# MCU.net
KiCad netlist of a schematic drawn in Altium Designer
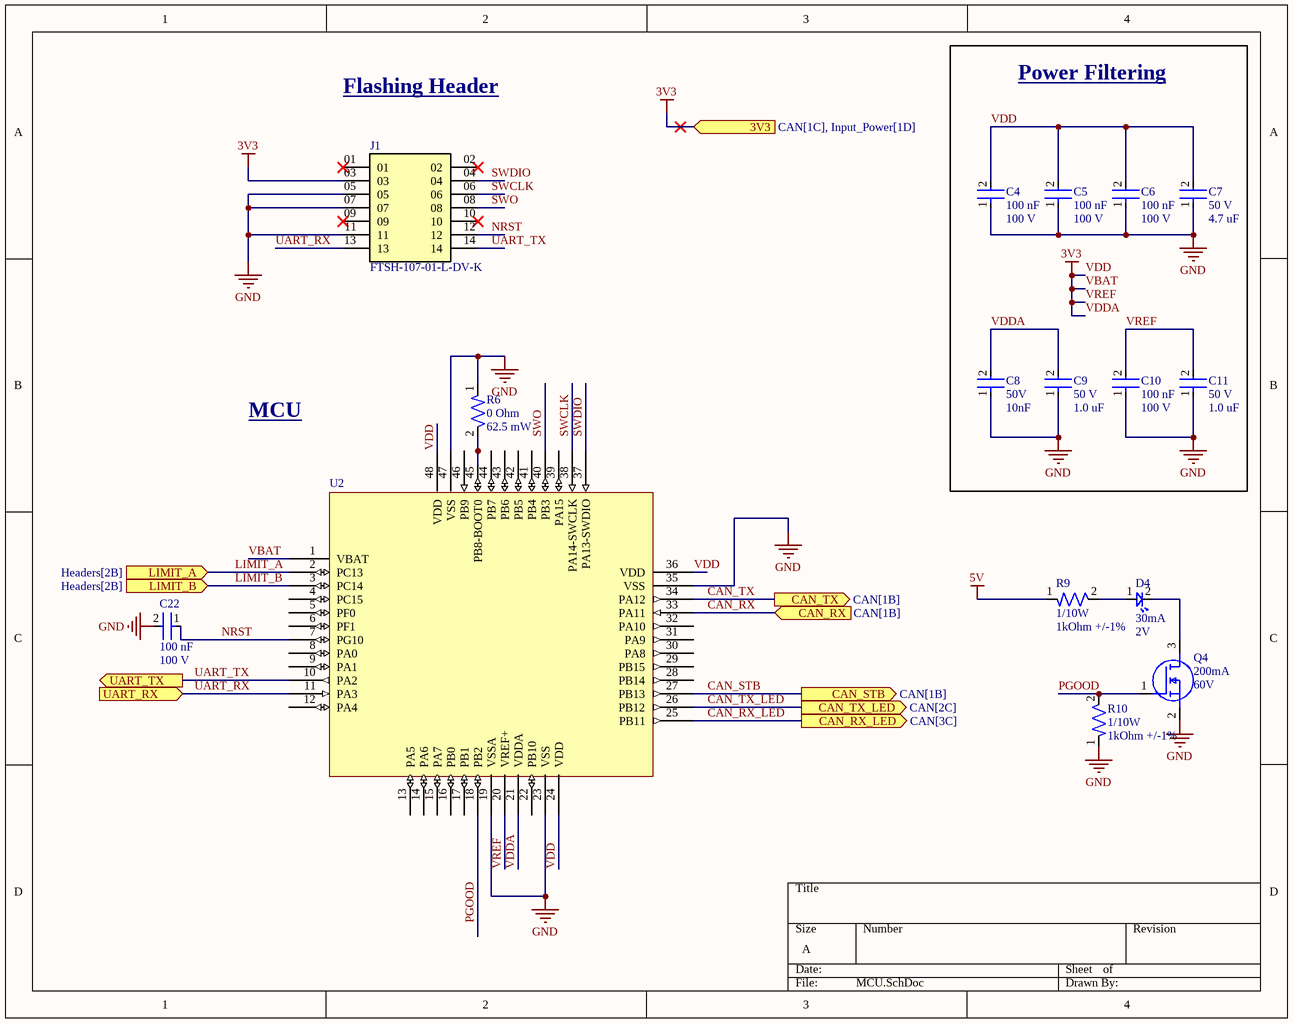
[diagram p0: MCU.SchDoc]

(export (version "E")
  (design (tool "Eeschema 10.0.6"))
  (components
    (comp (ref "C4")
      (value "CC0603KRX7R0BB104")
      (footprint "CAP-0603")
      (description "CAP CER 0.1UF 100V X7R 0603")
      (fields (field (name "CAPACITANCE") "100 nF") (field (name "VOLTAGE") "100 V"))
      (libsource (lib "JLC_25") (part "CAP-100N-0001"))
    )
    (comp (ref "C5")
      (value "CC0603KRX7R0BB104")
      (footprint "CAP-0603")
      (description "CAP CER 0.1UF 100V X7R 0603")
      (fields (field (name "CAPACITANCE") "100 nF") (field (name "VOLTAGE") "100 V"))
      (libsource (lib "JLC_25") (part "CAP-100N-0001"))
    )
    (comp (ref "C6")
      (value "CC0603KRX7R0BB104")
      (footprint "CAP-0603")
      (description "CAP CER 0.1UF 100V X7R 0603")
      (fields (field (name "CAPACITANCE") "100 nF") (field (name "VOLTAGE") "100 V"))
      (libsource (lib "JLC_25") (part "CAP-100N-0001"))
    )
    (comp (ref "C7")
      (value "CC0805KKX5R9BB475")
      (footprint "CAP-0805")
      (description "CAP CER 4.7UF 50V X5R 0805")
      (fields (field (name "VOLTAGE") "50 V") (field (name "CAPACITANCE") "4.7 uF"))
      (libsource (lib "JLC_25") (part "CAP-4.7U-0002"))
    )
    (comp (ref "C8")
      (value "GRM2195C1H103JA01D")
      (footprint "CAP-0805")
      (description "CAP CER 10000PF 50V C0G/NP0 0805")
      (fields (field (name "VOLTAGE") "50V") (field (name "CAPACITANCE") "10nF"))
      (libsource (lib "JLC_25") (part "CAP-10N-0001"))
    )
    (comp (ref "C9")
      (value "CC0805KKX7R9BB105")
      (footprint "CAP-0805")
      (description "CAP CER 1UF 50V X7R 0805")
      (fields (field (name "VOLTAGE") "50 V") (field (name "CAPACITANCE") "1.0 uF"))
      (libsource (lib "JLC_25") (part "CAP-1U-0001"))
    )
    (comp (ref "C10")
      (value "CC0603KRX7R0BB104")
      (footprint "CAP-0603")
      (description "CAP CER 0.1UF 100V X7R 0603")
      (fields (field (name "CAPACITANCE") "100 nF") (field (name "VOLTAGE") "100 V"))
      (libsource (lib "JLC_25") (part "CAP-100N-0001"))
    )
    (comp (ref "C11")
      (value "CC0805KKX7R9BB105")
      (footprint "CAP-0805")
      (description "CAP CER 1UF 50V X7R 0805")
      (fields (field (name "VOLTAGE") "50 V") (field (name "CAPACITANCE") "1.0 uF"))
      (libsource (lib "JLC_25") (part "CAP-1U-0001"))
    )
    (comp (ref "C22")
      (value "CC0603KRX7R0BB104")
      (footprint "CAP-0603")
      (description "CAP CER 0.1UF 100V X7R 0603")
      (fields (field (name "CAPACITANCE") "100 nF") (field (name "VOLTAGE") "100 V"))
      (libsource (lib "JLC_25") (part "CAP-100N-0001"))
    )
    (comp (ref "D4")
      (value "BL-HKC36G-AV-TRB")
      (footprint "LED-0603")
      (description "LED YELLOW CLEAR 0603 SMD")
      (fields (field (name "FORWARD CURRENT") "30mA") (field (name "FORWARD VOLTAGE") "2V"))
      (libsource (lib "JLC_25") (part "LED-0001"))
    )
    (comp (ref "J1")
      (value "FTSH-107-01-L-DV-K")
      (footprint "SAMTEC_FTSH-107-01-L-DV-K")
      (description "Connector Header Surface Mount 14 position 0.050\" (1.27mm)")
      (fields (field (name "MF") "Samtec"))
      (libsource (lib "MasterLib") (part "CONN_Flashing-0001"))
    )
    (comp (ref "Q4")
      (value "T2N7002AK,LM")
      (footprint "IC-SOT23-3")
      (description "MOSFET N-CH 60V 200MA SOT23")
      (fields (field (name "CONTINUOUS CURRENT") "200mA") (field (name "VOLTAGE") "60V"))
      (libsource (lib "JLC_25") (part "NMOS-200MA-0001"))
    )
    (comp (ref "R6")
      (value "RC0402FR-070RL")
      (footprint "RES-0402")
      (description "62.5mW Thick Film Resistors 50V -55℃~+155℃ 0Ω 0402 Chip Resistor - Surface Mount ROHS")
      (fields
        (field (name "JLC PART NUMBER") "C106231")
        (field (name "RESISTANCE") "0 Ohm")
        (field (name "POWER") "62.5 mW")
      )
      (libsource (lib "MasterLib") (part "RES-0-0002-JLC"))
    )
    (comp (ref "R9")
      (value "RT0603FRE131KL")
      (footprint "RES-0603")
      (description "1 kOhms ±1% 0.1W, 1/10W Chip Resistor 0603 (1608 Metric) Thin Film")
      (fields
        (field (name "MANUFACTURER") "YAGEO")
        (field (name "POWER RATING") "1/10W")
        (field (name "RESISTANCE") "1kOhm +/-1%")
      )
      (libsource (lib "MasterLib") (part "RES-1K-0002"))
    )
    (comp (ref "R10")
      (value "RT0603FRE131KL")
      (footprint "RES-0603")
      (description "1 kOhms ±1% 0.1W, 1/10W Chip Resistor 0603 (1608 Metric) Thin Film")
      (fields
        (field (name "MANUFACTURER") "YAGEO")
        (field (name "POWER RATING") "1/10W")
        (field (name "RESISTANCE") "1kOhm +/-1%")
      )
      (libsource (lib "MasterLib") (part "RES-1K-0002"))
    )
    (comp (ref "U2")
      (value "STM32G431CBT6")
      (footprint "IC-LQFP48")
      (description "IC MCU 32BIT 128KB FLASH 48LQFP")
      (libsource (lib "JLC_25") (part "IC-STM32G431CBT6"))
    )
  )
  (nets
    (net (code "1") (name "/CAN_RX") (class "Default")
      (node (ref "U2") (pin "33") (pinfunction "PA11_33") (pintype "input"))
    )
    (net (code "2") (name "/CAN_RX_LED") (class "Default")
      (node (ref "U2") (pin "25") (pinfunction "PB11_25") (pintype "output"))
    )
    (net (code "3") (name "/CAN_STB") (class "Default")
      (node (ref "U2") (pin "27") (pinfunction "PB13_27") (pintype "output"))
    )
    (net (code "4") (name "/CAN_TX") (class "Default")
      (node (ref "U2") (pin "34") (pinfunction "PA12_34") (pintype "output"))
    )
    (net (code "5") (name "/CAN_TX_LED") (class "Default")
      (node (ref "U2") (pin "26") (pinfunction "PB12_26") (pintype "output"))
    )
    (net (code "6") (name "/LIMIT_A") (class "Default")
      (node (ref "U2") (pin "2") (pinfunction "PC13_2") (pintype "bidirectional"))
    )
    (net (code "7") (name "/LIMIT_B") (class "Default")
      (node (ref "U2") (pin "3") (pinfunction "PC14_3") (pintype "bidirectional"))
    )
    (net (code "8") (name "/NRST") (class "Default")
      (node (ref "C22") (pin "1") (pinfunction "1_1") (pintype "passive"))
      (node (ref "J1") (pin "12") (pinfunction "12_12") (pintype "passive"))
      (node (ref "U2") (pin "7") (pinfunction "PG10_7") (pintype "bidirectional"))
    )
    (net (code "9") (name "/PGOOD") (class "Default")
      (node (ref "Q4") (pin "1") (pinfunction "G_1") (pintype "passive"))
      (node (ref "R10") (pin "2") (pinfunction "2_2") (pintype "passive"))
      (node (ref "U2") (pin "18") (pinfunction "PB2_18") (pintype "bidirectional"))
    )
    (net (code "10") (name "/SWCLK") (class "Default")
      (node (ref "J1") (pin "06") (pinfunction "06_06") (pintype "passive"))
      (node (ref "U2") (pin "38") (pinfunction "PA14-SWCLK_38") (pintype "input"))
    )
    (net (code "11") (name "/SWDIO") (class "Default")
      (node (ref "J1") (pin "04") (pinfunction "04_04") (pintype "passive"))
      (node (ref "U2") (pin "37") (pinfunction "PA13-SWDIO_37") (pintype "input"))
    )
    (net (code "12") (name "/SWO") (class "Default")
      (node (ref "J1") (pin "08") (pinfunction "08_08") (pintype "passive"))
      (node (ref "U2") (pin "40") (pinfunction "PB3_40") (pintype "bidirectional"))
    )
    (net (code "13") (name "/UART_RX") (class "Default")
      (node (ref "J1") (pin "13") (pinfunction "13_13") (pintype "passive"))
      (node (ref "U2") (pin "11") (pinfunction "PA3_11") (pintype "input"))
    )
    (net (code "14") (name "/UART_TX") (class "Default")
      (node (ref "J1") (pin "14") (pinfunction "14_14") (pintype "passive"))
      (node (ref "U2") (pin "10") (pinfunction "PA2_10") (pintype "output"))
    )
    (net (code "15") (name "3V3") (class "Default")
      (node (ref "C10") (pin "2") (pinfunction "2_2") (pintype "passive"))
      (node (ref "C11") (pin "2") (pinfunction "2_2") (pintype "passive"))
      (node (ref "C4") (pin "2") (pinfunction "2_2") (pintype "passive"))
      (node (ref "C5") (pin "2") (pinfunction "2_2") (pintype "passive"))
      (node (ref "C6") (pin "2") (pinfunction "2_2") (pintype "passive"))
      (node (ref "C7") (pin "2") (pinfunction "2_2") (pintype "passive"))
      (node (ref "C8") (pin "2") (pinfunction "2_2") (pintype "passive"))
      (node (ref "C9") (pin "2") (pinfunction "2_2") (pintype "passive"))
      (node (ref "J1") (pin "03") (pinfunction "03_03") (pintype "passive"))
      (node (ref "U2") (pin "1") (pinfunction "VBAT_1") (pintype "power_in"))
      (node (ref "U2") (pin "20") (pinfunction "VREF+_20") (pintype "power_in"))
      (node (ref "U2") (pin "21") (pinfunction "VDDA_21") (pintype "power_in"))
      (node (ref "U2") (pin "24") (pinfunction "VDD_24") (pintype "power_in"))
      (node (ref "U2") (pin "36") (pinfunction "VDD_36") (pintype "power_in"))
      (node (ref "U2") (pin "48") (pinfunction "VDD_48") (pintype "power_in"))
    )
    (net (code "16") (name "5V") (class "Default")
      (node (ref "R9") (pin "1") (pinfunction "1_1") (pintype "passive"))
    )
    (net (code "17") (name "GND") (class "Default")
      (node (ref "C10") (pin "1") (pinfunction "1_1") (pintype "passive"))
      (node (ref "C11") (pin "1") (pinfunction "1_1") (pintype "passive"))
      (node (ref "C22") (pin "2") (pinfunction "2_2") (pintype "passive"))
      (node (ref "C4") (pin "1") (pinfunction "1_1") (pintype "passive"))
      (node (ref "C5") (pin "1") (pinfunction "1_1") (pintype "passive"))
      (node (ref "C6") (pin "1") (pinfunction "1_1") (pintype "passive"))
      (node (ref "C7") (pin "1") (pinfunction "1_1") (pintype "passive"))
      (node (ref "C8") (pin "1") (pinfunction "1_1") (pintype "passive"))
      (node (ref "C9") (pin "1") (pinfunction "1_1") (pintype "passive"))
      (node (ref "J1") (pin "05") (pinfunction "05_05") (pintype "passive"))
      (node (ref "J1") (pin "07") (pinfunction "07_07") (pintype "passive"))
      (node (ref "J1") (pin "11") (pinfunction "11_11") (pintype "passive"))
      (node (ref "Q4") (pin "2") (pinfunction "S_2") (pintype "passive"))
      (node (ref "R10") (pin "1") (pinfunction "1_1") (pintype "passive"))
      (node (ref "R6") (pin "1") (pinfunction "1_1") (pintype "passive"))
      (node (ref "U2") (pin "19") (pinfunction "VSSA_19") (pintype "power_in"))
      (node (ref "U2") (pin "23") (pinfunction "VSS_23") (pintype "power_in"))
      (node (ref "U2") (pin "35") (pinfunction "VSS_35") (pintype "power_in"))
      (node (ref "U2") (pin "47") (pinfunction "VSS_47") (pintype "power_in"))
    )
    (net (code "18") (name "Net-(D4-Pad1)") (class "Default")
      (node (ref "D4") (pin "1") (pinfunction "1_1") (pintype "passive"))
      (node (ref "R9") (pin "2") (pinfunction "2_2") (pintype "passive"))
    )
    (net (code "19") (name "Net-(Q4-D)") (class "Default")
      (node (ref "D4") (pin "2") (pinfunction "2_2") (pintype "passive"))
      (node (ref "Q4") (pin "3") (pinfunction "D_3") (pintype "passive"))
    )
    (net (code "20") (name "Net-(U2-PB8-BOOT0)") (class "Default")
      (node (ref "R6") (pin "2") (pinfunction "2_2") (pintype "passive"))
      (node (ref "U2") (pin "45") (pinfunction "PB8-BOOT0_45") (pintype "bidirectional"))
    )
    (net (code "21") (name "unconnected-(J1-Pad01)") (class "Default")
      (node (ref "J1") (pin "01") (pinfunction "01_01") (pintype "passive+no_connect"))
    )
    (net (code "22") (name "unconnected-(J1-Pad02)") (class "Default")
      (node (ref "J1") (pin "02") (pinfunction "02_02") (pintype "passive+no_connect"))
    )
    (net (code "23") (name "unconnected-(J1-Pad09)") (class "Default")
      (node (ref "J1") (pin "09") (pinfunction "09_09") (pintype "passive+no_connect"))
    )
    (net (code "24") (name "unconnected-(J1-Pad10)") (class "Default")
      (node (ref "J1") (pin "10") (pinfunction "10_10") (pintype "passive+no_connect"))
    )
    (net (code "25") (name "unconnected-(U2-PA0-Pad8)") (class "Default")
      (node (ref "U2") (pin "8") (pinfunction "PA0_8") (pintype "bidirectional"))
    )
    (net (code "26") (name "unconnected-(U2-PA1-Pad9)") (class "Default")
      (node (ref "U2") (pin "9") (pinfunction "PA1_9") (pintype "bidirectional"))
    )
    (net (code "27") (name "unconnected-(U2-PA4-Pad12)") (class "Default")
      (node (ref "U2") (pin "12") (pinfunction "PA4_12") (pintype "bidirectional"))
    )
    (net (code "28") (name "unconnected-(U2-PA5-Pad13)") (class "Default")
      (node (ref "U2") (pin "13") (pinfunction "PA5_13") (pintype "bidirectional"))
    )
    (net (code "29") (name "unconnected-(U2-PA6-Pad14)") (class "Default")
      (node (ref "U2") (pin "14") (pinfunction "PA6_14") (pintype "bidirectional"))
    )
    (net (code "30") (name "unconnected-(U2-PA7-Pad15)") (class "Default")
      (node (ref "U2") (pin "15") (pinfunction "PA7_15") (pintype "bidirectional"))
    )
    (net (code "31") (name "unconnected-(U2-PA8-Pad30)") (class "Default")
      (node (ref "U2") (pin "30") (pinfunction "PA8_30") (pintype "output"))
    )
    (net (code "32") (name "unconnected-(U2-PA9-Pad31)") (class "Default")
      (node (ref "U2") (pin "31") (pinfunction "PA9_31") (pintype "output"))
    )
    (net (code "33") (name "unconnected-(U2-PA10-Pad32)") (class "Default")
      (node (ref "U2") (pin "32") (pinfunction "PA10_32") (pintype "output"))
    )
    (net (code "34") (name "unconnected-(U2-PA15-Pad39)") (class "Default")
      (node (ref "U2") (pin "39") (pinfunction "PA15_39") (pintype "bidirectional"))
    )
    (net (code "35") (name "unconnected-(U2-PB0-Pad16)") (class "Default")
      (node (ref "U2") (pin "16") (pinfunction "PB0_16") (pintype "bidirectional"))
    )
    (net (code "36") (name "unconnected-(U2-PB1-Pad17)") (class "Default")
      (node (ref "U2") (pin "17") (pinfunction "PB1_17") (pintype "bidirectional"))
    )
    (net (code "37") (name "unconnected-(U2-PB4-Pad41)") (class "Default")
      (node (ref "U2") (pin "41") (pinfunction "PB4_41") (pintype "bidirectional"))
    )
    (net (code "38") (name "unconnected-(U2-PB5-Pad42)") (class "Default")
      (node (ref "U2") (pin "42") (pinfunction "PB5_42") (pintype "bidirectional"))
    )
    (net (code "39") (name "unconnected-(U2-PB6-Pad43)") (class "Default")
      (node (ref "U2") (pin "43") (pinfunction "PB6_43") (pintype "bidirectional"))
    )
    (net (code "40") (name "unconnected-(U2-PB7-Pad44)") (class "Default")
      (node (ref "U2") (pin "44") (pinfunction "PB7_44") (pintype "bidirectional"))
    )
    (net (code "41") (name "unconnected-(U2-PB9-Pad46)") (class "Default")
      (node (ref "U2") (pin "46") (pinfunction "PB9_46") (pintype "input"))
    )
    (net (code "42") (name "unconnected-(U2-PB10-Pad22)") (class "Default")
      (node (ref "U2") (pin "22") (pinfunction "PB10_22") (pintype "bidirectional"))
    )
    (net (code "43") (name "unconnected-(U2-PB14-Pad28)") (class "Default")
      (node (ref "U2") (pin "28") (pinfunction "PB14_28") (pintype "output"))
    )
    (net (code "44") (name "unconnected-(U2-PB15-Pad29)") (class "Default")
      (node (ref "U2") (pin "29") (pinfunction "PB15_29") (pintype "output"))
    )
    (net (code "45") (name "unconnected-(U2-PC15-Pad4)") (class "Default")
      (node (ref "U2") (pin "4") (pinfunction "PC15_4") (pintype "bidirectional"))
    )
    (net (code "46") (name "unconnected-(U2-PF0-Pad5)") (class "Default")
      (node (ref "U2") (pin "5") (pinfunction "PF0_5") (pintype "bidirectional"))
    )
    (net (code "47") (name "unconnected-(U2-PF1-Pad6)") (class "Default")
      (node (ref "U2") (pin "6") (pinfunction "PF1_6") (pintype "bidirectional"))
    )
  )
)
